# Module_T_H_02v.net
KiCad netlist of a schematic drawn in EAGLE
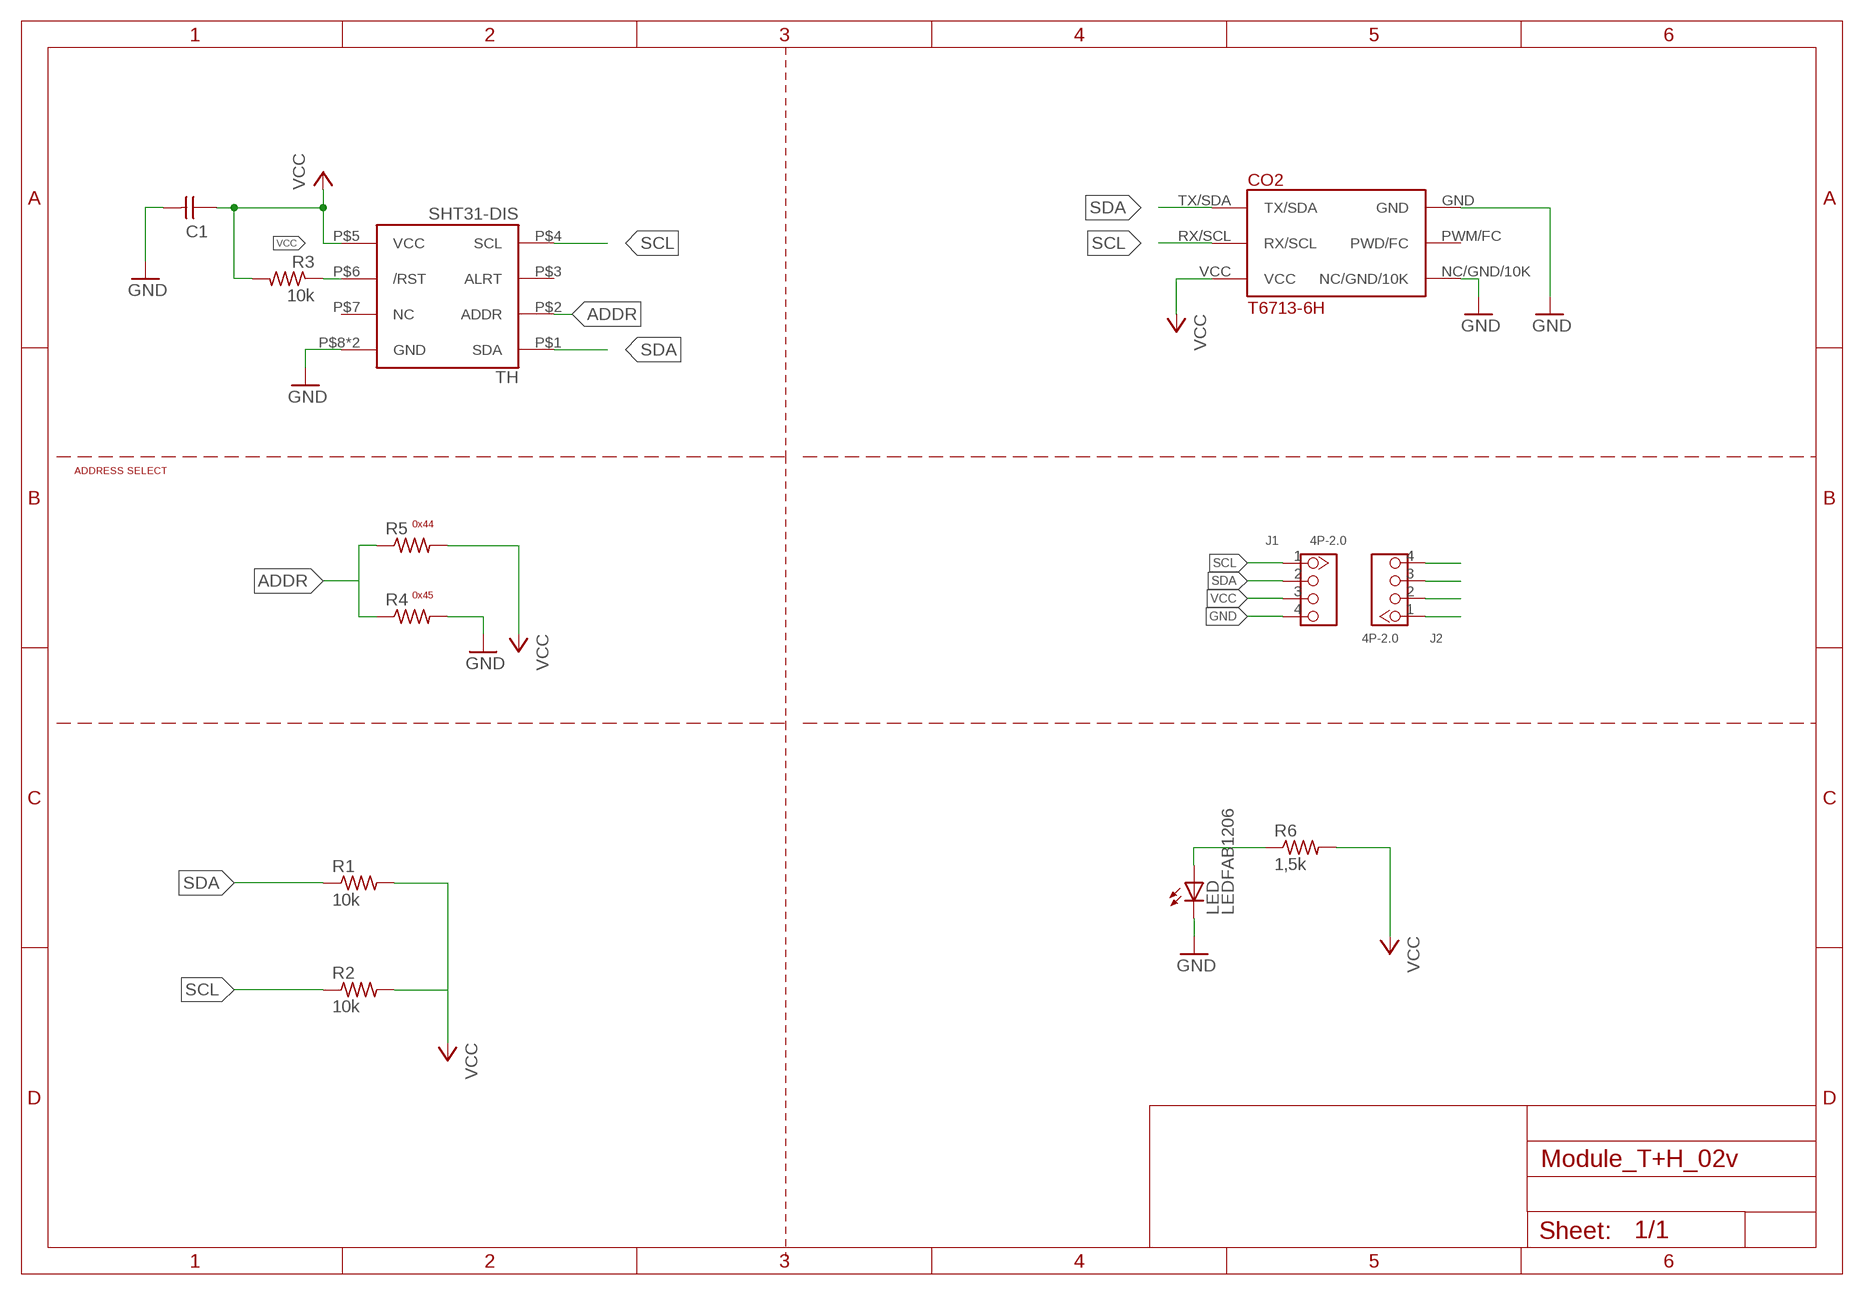
[diagram p0: schematic, sheet 1]

(export (version "E")
  (design (tool "Eeschema 10.0.6"))
  (components
    (comp (ref "C1")
      (value "CAP-UNPOLARIZEDFAB")
      (footprint "eagle-import:C1206FAB")
      (libsource (lib "eagle-import") (part "CAP-UNPOLARIZEDFAB"))
    )
    (comp (ref "CO2")
      (value "T6713-6H")
      (footprint "eagle-import:PINS")
      (libsource (lib "eagle-import") (part "T6713-6H"))
    )
    (comp (ref "J1")
      (value "4P-2.0")
      (footprint "eagle-import:HW4-2.0")
      (libsource (lib "eagle-import") (part "GROVE-CONNECTOR-DIP(4P-2.0)"))
    )
    (comp (ref "J2")
      (value "4P-2.0")
      (footprint "eagle-import:HW4-2.0")
      (libsource (lib "eagle-import") (part "GROVE-CONNECTOR-DIP(4P-2.0)"))
    )
    (comp (ref "LED")
      (value "LEDFAB1206")
      (footprint "eagle-import:LED1206FAB")
      (libsource (lib "eagle-import") (part "LEDFAB1206"))
    )
    (comp (ref "R1")
      (value "10k")
      (footprint "eagle-import:R1206FAB")
      (libsource (lib "eagle-import") (part "RES-US1206FAB"))
    )
    (comp (ref "R2")
      (value "10k")
      (footprint "eagle-import:R1206FAB")
      (libsource (lib "eagle-import") (part "RES-US1206FAB"))
    )
    (comp (ref "R3")
      (value "10k")
      (footprint "eagle-import:R1206FAB")
      (libsource (lib "eagle-import") (part "RES-US1206FAB"))
    )
    (comp (ref "R4")
      (value "RES-US1206FAB")
      (footprint "eagle-import:R1206FAB")
      (libsource (lib "eagle-import") (part "RES-US1206FAB"))
    )
    (comp (ref "R5")
      (value "RES-US1206FAB")
      (footprint "eagle-import:R1206FAB")
      (libsource (lib "eagle-import") (part "RES-US1206FAB"))
    )
    (comp (ref "R6")
      (value "1,5k")
      (footprint "eagle-import:R1206FAB")
      (libsource (lib "eagle-import") (part "RES-US1206FAB"))
    )
    (comp (ref "TH")
      (value "SHT31-DIS")
      (footprint "eagle-import:SHT3X")
      (libsource (lib "eagle-import") (part "SHT31-DIS"))
    )
  )
  (nets
    (net (code "1") (name "ADDR") (class "Default")
      (node (ref "R4") (pin "1") (pinfunction "1_1") (pintype "passive"))
      (node (ref "R5") (pin "1") (pinfunction "1_1") (pintype "passive"))
      (node (ref "TH") (pin "P$2") (pinfunction "ADDR_P$2") (pintype "bidirectional"))
    )
    (net (code "2") (name "GND") (class "Default")
      (node (ref "C1") (pin "2") (pinfunction "2_2") (pintype "passive"))
      (node (ref "CO2") (pin "GND") (pinfunction "GND_GND") (pintype "bidirectional"))
      (node (ref "CO2") (pin "NC/GND/10K") (pinfunction "NC/GND/10K_NC/GND/10K") (pintype "bidirectional"))
      (node (ref "J1") (pin "4") (pinfunction "4_4") (pintype "bidirectional"))
      (node (ref "LED") (pin "2") (pinfunction "C_2") (pintype "passive"))
      (node (ref "R4") (pin "2") (pinfunction "2_2") (pintype "passive"))
      (node (ref "TH") (pin "P$8") (pinfunction "GND_P$8") (pintype "bidirectional"))
      (node (ref "TH") (pin "PAD") (pinfunction "GND_PAD") (pintype "bidirectional"))
    )
    (net (code "3") (name "Net-(LED-A)") (class "Default")
      (node (ref "LED") (pin "1") (pinfunction "A_1") (pintype "passive"))
      (node (ref "R6") (pin "1") (pinfunction "1_1") (pintype "passive"))
    )
    (net (code "4") (name "Net-(TH-{slash}RST)") (class "Default")
      (node (ref "R3") (pin "1") (pinfunction "1_1") (pintype "passive"))
      (node (ref "TH") (pin "P$6") (pinfunction "/RST_P$6") (pintype "bidirectional"))
    )
    (net (code "5") (name "SCL") (class "Default")
      (node (ref "CO2") (pin "RX/SCL") (pinfunction "RX/SCL_RX/SCL") (pintype "bidirectional"))
      (node (ref "J1") (pin "1") (pinfunction "1_1") (pintype "bidirectional"))
      (node (ref "R2") (pin "1") (pinfunction "1_1") (pintype "passive"))
      (node (ref "TH") (pin "P$4") (pinfunction "SCL_P$4") (pintype "bidirectional"))
    )
    (net (code "6") (name "SDA") (class "Default")
      (node (ref "CO2") (pin "TX/SDA") (pinfunction "TX/SDA_TX/SDA") (pintype "bidirectional"))
      (node (ref "J1") (pin "2") (pinfunction "2_2") (pintype "bidirectional"))
      (node (ref "R1") (pin "1") (pinfunction "1_1") (pintype "passive"))
      (node (ref "TH") (pin "P$1") (pinfunction "SDA_P$1") (pintype "bidirectional"))
    )
    (net (code "7") (name "VCC") (class "Default")
      (node (ref "C1") (pin "1") (pinfunction "1_1") (pintype "passive"))
      (node (ref "CO2") (pin "VCC") (pinfunction "VCC_VCC") (pintype "bidirectional"))
      (node (ref "J1") (pin "3") (pinfunction "3_3") (pintype "bidirectional"))
      (node (ref "R1") (pin "2") (pinfunction "2_2") (pintype "passive"))
      (node (ref "R2") (pin "2") (pinfunction "2_2") (pintype "passive"))
      (node (ref "R3") (pin "2") (pinfunction "2_2") (pintype "passive"))
      (node (ref "R5") (pin "2") (pinfunction "2_2") (pintype "passive"))
      (node (ref "R6") (pin "2") (pinfunction "2_2") (pintype "passive"))
      (node (ref "TH") (pin "P$5") (pinfunction "VCC_P$5") (pintype "bidirectional"))
    )
    (net (code "8") (name "unconnected-(CO2-PWD{slash}FC-PadPWM{slash}FC)") (class "Default")
      (node (ref "CO2") (pin "PWM/FC") (pinfunction "PWD/FC_PWM/FC") (pintype "bidirectional"))
    )
    (net (code "9") (name "unconnected-(J2-Pad1)") (class "Default")
      (node (ref "J2") (pin "1") (pinfunction "1_1") (pintype "bidirectional"))
    )
    (net (code "10") (name "unconnected-(J2-Pad2)") (class "Default")
      (node (ref "J2") (pin "2") (pinfunction "2_2") (pintype "bidirectional"))
    )
    (net (code "11") (name "unconnected-(J2-Pad3)") (class "Default")
      (node (ref "J2") (pin "3") (pinfunction "3_3") (pintype "bidirectional"))
    )
    (net (code "12") (name "unconnected-(J2-Pad4)") (class "Default")
      (node (ref "J2") (pin "4") (pinfunction "4_4") (pintype "bidirectional"))
    )
    (net (code "13") (name "unconnected-(TH-ALRT-PadP$3)") (class "Default")
      (node (ref "TH") (pin "P$3") (pinfunction "ALRT_P$3") (pintype "bidirectional"))
    )
    (net (code "14") (name "unconnected-(TH-NC-PadP$7)") (class "Default")
      (node (ref "TH") (pin "P$7") (pinfunction "NC_P$7") (pintype "bidirectional"))
    )
  )
)
